# AUX_power_board.net
KiCad netlist of a schematic drawn in EAGLE
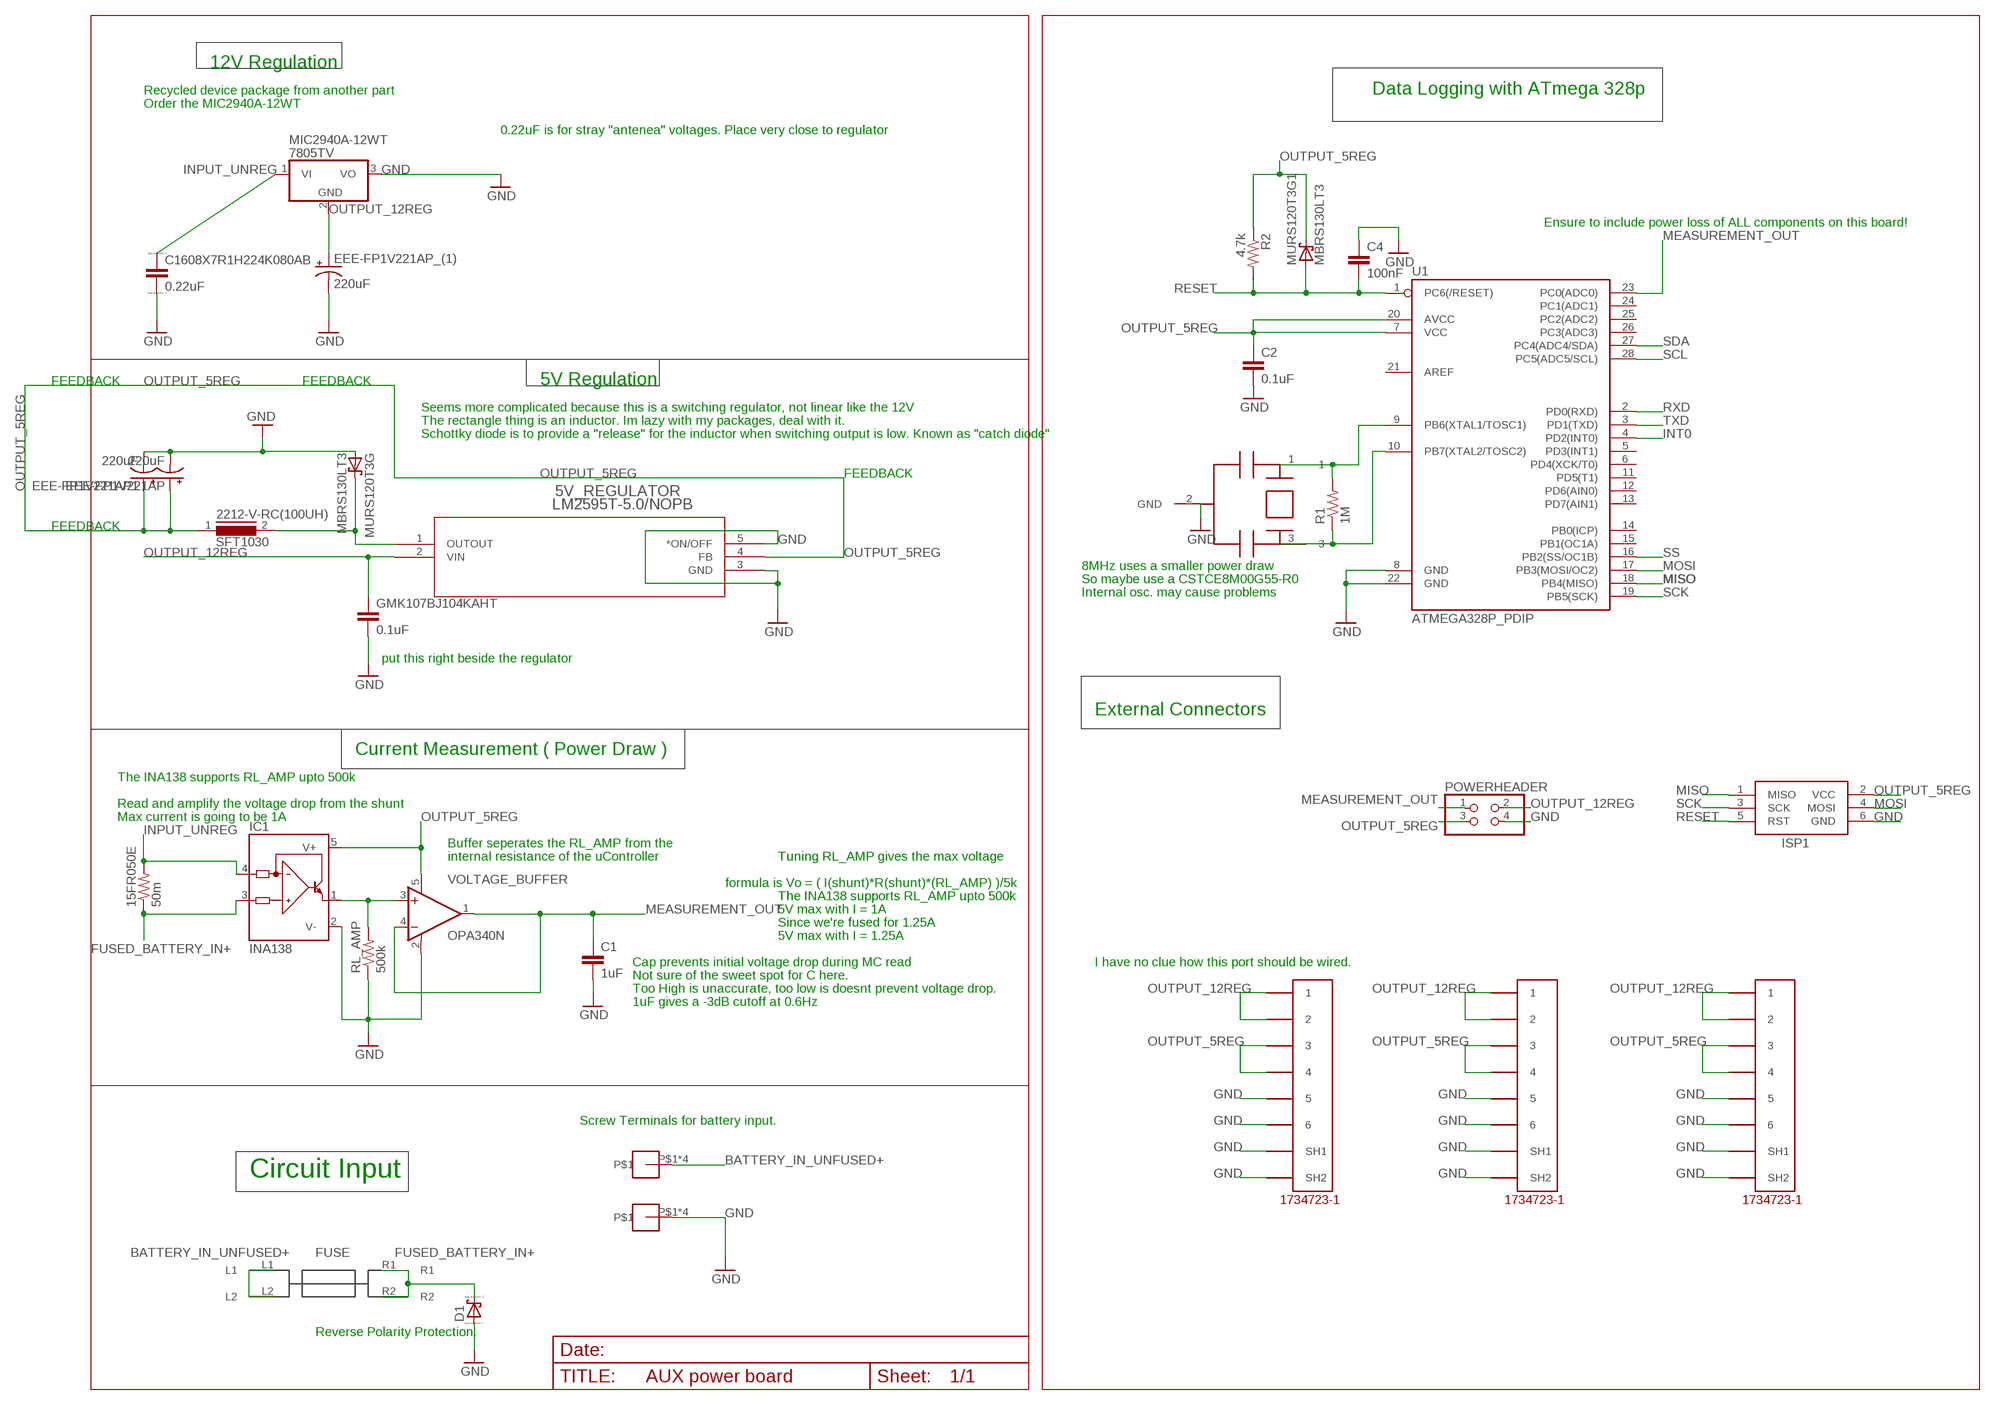
[diagram p0: schematic, sheet 1]

(export (version "E")
  (design (tool "Eeschema 10.0.6"))
  (components
    (comp (ref "5V_REGULATOR")
      (value "LM2595T-5.0/NOPB")
      (footprint "eagle-import:T05D")
      (fields
        (field (name "MANUFACTURER_PART_NUMBER") "LM2595T50")
        (field (name "COPYRIGHT") "Copyright C 2015 Accelerated Designs. All rights reserved")
      )
      (libsource (lib "eagle-import") (part "LM2595T-5.0/NOPB"))
    )
    (comp (ref "15FR050E")
      (value "50m")
      (footprint "eagle-import:0617_22")
      (libsource (lib "eagle-import") (part "resistor_R-US_0617/22"))
    )
    (comp (ref "2212-V-RC(100UH)")
      (value "SFT1030")
      (footprint "eagle-import:SFT1030")
      (libsource (lib "eagle-import") (part "SFT1030"))
    )
    (comp (ref "C1")
      (value "1uF")
      (footprint "eagle-import:C0603")
      (libsource (lib "eagle-import") (part "resistor_C-EUC0603"))
    )
    (comp (ref "C2")
      (value "0.1uF")
      (footprint "eagle-import:C0603")
      (libsource (lib "eagle-import") (part "resistor_C-EUC0603"))
    )
    (comp (ref "C4")
      (value "100nF")
      (footprint "eagle-import:C0603")
      (libsource (lib "eagle-import") (part "C-EUC0603"))
    )
    (comp (ref "C1608X7R1H224K080AB")
      (value "0.22uF")
      (footprint "eagle-import:C0603")
      (libsource (lib "eagle-import") (part "CC0603"))
    )
    (comp (ref "D1")
      (value "SCHOTTKY-DIODESMC")
      (footprint "eagle-import:DIODE_SMC")
      (libsource (lib "eagle-import") (part "SCHOTTKY-DIODESMC"))
    )
    (comp (ref "EEE-FP1V221AP")
      (value "220uF")
      (footprint "eagle-import:175TMP-0808")
      (libsource (lib "eagle-import") (part "CPOL-US175TMP-0808"))
    )
    (comp (ref "EEE-FP1V221AP1")
      (value "220uF")
      (footprint "eagle-import:175TMP-0808")
      (libsource (lib "eagle-import") (part "CPOL-US175TMP-0808"))
    )
    (comp (ref "EEE-FP1V221AP_(1)")
      (value "220uF")
      (footprint "eagle-import:175TMP-0808")
      (libsource (lib "eagle-import") (part "CPOL-US175TMP-0808"))
    )
    (comp (ref "GMK107BJ104KAHT")
      (value "0.1uF")
      (footprint "eagle-import:C0603")
      (libsource (lib "eagle-import") (part "C-EUC0603"))
    )
    (comp (ref "IC1")
      (value "INA138")
      (footprint "eagle-import:SOT23-5")
      (fields (field (name "MF") "TEXAS INSTRUMENTS") (field (name "MPN") "INA138NA/250"))
      (libsource (lib "eagle-import") (part "INA138"))
    )
    (comp (ref "ISP1")
      (value "AVRISP-6")
      (footprint "eagle-import:AVRISP")
      (libsource (lib "eagle-import") (part "AVRISP-6"))
    )
    (comp (ref "MIC2940A-12WT")
      (value "7805TV")
      (footprint "eagle-import:TO220V")
      (libsource (lib "eagle-import") (part "78TV05"))
    )
    (comp (ref "MINIBLADE")
      (value "3568")
      (footprint "eagle-import:3568")
      (libsource (lib "eagle-import") (part "3568"))
    )
    (comp (ref "MURS120T3G")
      (value "MBRS130LT3")
      (footprint "eagle-import:SMB")
      (libsource (lib "eagle-import") (part "MBRS130LT3"))
    )
    (comp (ref "MURS120T3G1")
      (value "MBRS130LT3")
      (footprint "eagle-import:SMB")
      (libsource (lib "eagle-import") (part "MBRS130LT3"))
    )
    (comp (ref "POWERHEADER")
      (value "PINHD-2X2")
      (footprint "eagle-import:2X02")
      (libsource (lib "eagle-import") (part "PINHD-2X2"))
    )
    (comp (ref "R1")
      (value "1M")
      (footprint "eagle-import:R0603")
      (libsource (lib "eagle-import") (part "R-US_R0603"))
    )
    (comp (ref "R2")
      (value "4.7k")
      (footprint "eagle-import:R0603")
      (libsource (lib "eagle-import") (part "resistor_R-US_R0603"))
    )
    (comp (ref "RL_AMP")
      (value "500k")
      (footprint "eagle-import:R0603")
      (libsource (lib "eagle-import") (part "resistor_R-US_R0603"))
    )
    (comp (ref "U$1")
      (value "CSTCE16M0V53-R0")
      (footprint "eagle-import:RESONATOR")
      (libsource (lib "eagle-import") (part "CSTCE16M0V53-R0"))
    )
    (comp (ref "U$3")
      (value "5555140-6")
      (footprint "eagle-import:1734723-1_RJ11")
      (libsource (lib "eagle-import") (part "5555140-6"))
    )
    (comp (ref "U$4")
      (value "5555140-6")
      (footprint "eagle-import:1734723-1_RJ11")
      (libsource (lib "eagle-import") (part "5555140-6"))
    )
    (comp (ref "U$5")
      (value "5555140-6")
      (footprint "eagle-import:1734723-1_RJ11")
      (libsource (lib "eagle-import") (part "5555140-6"))
    )
    (comp (ref "U$6")
      (value "SCREW-8191")
      (footprint "eagle-import:SCREW-8191")
      (libsource (lib "eagle-import") (part "SCREW-8191"))
    )
    (comp (ref "U$7")
      (value "SCREW-8191")
      (footprint "eagle-import:SCREW-8191")
      (libsource (lib "eagle-import") (part "SCREW-8191"))
    )
    (comp (ref "U1")
      (value "ATMEGA328P_PDIP")
      (footprint "eagle-import:DIL28-3")
      (libsource (lib "eagle-import") (part "ATMEGA328P_PDIP"))
    )
    (comp (ref "VOLTAGE_BUFFER")
      (value "OPA340N")
      (footprint "eagle-import:SOT23-5")
      (fields (field (name "MPN") "OPA340NA/3KG4"))
      (libsource (lib "eagle-import") (part "OPA340N"))
    )
  )
  (nets
    (net (code "1") (name "/BATTERY_IN_UNFUSED+") (class "Default")
      (node (ref "MINIBLADE") (pin "L1") (pinfunction "L1_L1") (pintype "bidirectional"))
      (node (ref "MINIBLADE") (pin "L2") (pinfunction "L2_L2") (pintype "bidirectional"))
      (node (ref "U$6") (pin "P$1") (pinfunction "P$1_P$1") (pintype "bidirectional"))
      (node (ref "U$6") (pin "P$2") (pinfunction "P$1_P$2") (pintype "bidirectional"))
      (node (ref "U$6") (pin "P$3") (pinfunction "P$1_P$3") (pintype "bidirectional"))
      (node (ref "U$6") (pin "P$4") (pinfunction "P$1_P$4") (pintype "bidirectional"))
    )
    (net (code "2") (name "/FUSED_BATTERY_IN+") (class "Default")
      (node (ref "15FR050E") (pin "1") (pinfunction "1_1") (pintype "passive"))
      (node (ref "D1") (pin "C") (pinfunction "A_C") (pintype "passive"))
      (node (ref "IC1") (pin "3") (pinfunction "IN+_3") (pintype "input"))
      (node (ref "MINIBLADE") (pin "R1") (pinfunction "R1_R1") (pintype "bidirectional"))
      (node (ref "MINIBLADE") (pin "R2") (pinfunction "R2_R2") (pintype "bidirectional"))
    )
    (net (code "3") (name "/INPUT_UNREG") (class "Default")
      (node (ref "15FR050E") (pin "2") (pinfunction "2_2") (pintype "passive"))
      (node (ref "C1608X7R1H224K080AB") (pin "1") (pinfunction "1_1") (pintype "passive"))
      (node (ref "IC1") (pin "4") (pinfunction "IN-_4") (pintype "input"))
      (node (ref "MIC2940A-12WT") (pin "1") (pinfunction "VI_1") (pintype "input"))
    )
    (net (code "4") (name "/INT0") (class "Default")
      (node (ref "U1") (pin "4") (pinfunction "PD2(INT0)_4") (pintype "bidirectional"))
    )
    (net (code "5") (name "/MEASUREMENT_OUT") (class "Default")
      (node (ref "C1") (pin "1") (pinfunction "1_1") (pintype "passive"))
      (node (ref "POWERHEADER") (pin "1") (pinfunction "1_1") (pintype "passive"))
      (node (ref "U1") (pin "23") (pinfunction "PC0(ADC0)_23") (pintype "bidirectional"))
      (node (ref "VOLTAGE_BUFFER") (pin "1") (pinfunction "OUT_1") (pintype "output"))
      (node (ref "VOLTAGE_BUFFER") (pin "4") (pinfunction "-IN_4") (pintype "input"))
    )
    (net (code "6") (name "/MISO") (class "Default")
      (node (ref "ISP1") (pin "1") (pinfunction "MISO_1") (pintype "input"))
      (node (ref "U1") (pin "18") (pinfunction "PB4(MISO)_18") (pintype "bidirectional"))
    )
    (net (code "7") (name "/MOSI") (class "Default")
      (node (ref "ISP1") (pin "4") (pinfunction "MOSI_4") (pintype "output"))
      (node (ref "U1") (pin "17") (pinfunction "PB3(MOSI/OC2)_17") (pintype "bidirectional"))
    )
    (net (code "8") (name "/OUTPUT_5REG") (class "Default")
      (node (ref "2212-V-RC(100UH)") (pin "1") (pinfunction "1_1") (pintype "passive"))
      (node (ref "5V_REGULATOR") (pin "4") (pinfunction "FB_4") (pintype "passive"))
      (node (ref "C2") (pin "1") (pinfunction "1_1") (pintype "passive"))
      (node (ref "EEE-FP1V221AP") (pin "+") (pinfunction "+_+") (pintype "passive"))
      (node (ref "EEE-FP1V221AP1") (pin "+") (pinfunction "+_+") (pintype "passive"))
      (node (ref "IC1") (pin "5") (pinfunction "V+_5") (pintype "power_in"))
      (node (ref "ISP1") (pin "2") (pinfunction "VCC_2") (pintype "power_in"))
      (node (ref "MURS120T3G1") (pin "C") (pinfunction "C_C") (pintype "passive"))
      (node (ref "POWERHEADER") (pin "3") (pinfunction "3_3") (pintype "passive"))
      (node (ref "R2") (pin "1") (pinfunction "1_1") (pintype "passive"))
      (node (ref "U$3") (pin "3") (pinfunction "3_3") (pintype "bidirectional"))
      (node (ref "U$3") (pin "4") (pinfunction "4_4") (pintype "bidirectional"))
      (node (ref "U$4") (pin "3") (pinfunction "3_3") (pintype "bidirectional"))
      (node (ref "U$4") (pin "4") (pinfunction "4_4") (pintype "bidirectional"))
      (node (ref "U$5") (pin "3") (pinfunction "3_3") (pintype "bidirectional"))
      (node (ref "U$5") (pin "4") (pinfunction "4_4") (pintype "bidirectional"))
      (node (ref "U1") (pin "20") (pinfunction "AVCC_20") (pintype "bidirectional"))
      (node (ref "U1") (pin "7") (pinfunction "VCC_7") (pintype "bidirectional"))
      (node (ref "VOLTAGE_BUFFER") (pin "5") (pinfunction "V+_5") (pintype "power_in"))
    )
    (net (code "9") (name "/OUTPUT_12REG") (class "Default")
      (node (ref "5V_REGULATOR") (pin "2") (pinfunction "VIN_2") (pintype "input"))
      (node (ref "EEE-FP1V221AP_(1)") (pin "+") (pinfunction "+_+") (pintype "passive"))
      (node (ref "GMK107BJ104KAHT") (pin "1") (pinfunction "1_1") (pintype "passive"))
      (node (ref "MIC2940A-12WT") (pin "2") (pinfunction "GND_2") (pintype "passive"))
      (node (ref "POWERHEADER") (pin "2") (pinfunction "2_2") (pintype "passive"))
      (node (ref "U$3") (pin "1") (pinfunction "1_1") (pintype "bidirectional"))
      (node (ref "U$3") (pin "2") (pinfunction "2_2") (pintype "bidirectional"))
      (node (ref "U$4") (pin "1") (pinfunction "1_1") (pintype "bidirectional"))
      (node (ref "U$4") (pin "2") (pinfunction "2_2") (pintype "bidirectional"))
      (node (ref "U$5") (pin "1") (pinfunction "1_1") (pintype "bidirectional"))
      (node (ref "U$5") (pin "2") (pinfunction "2_2") (pintype "bidirectional"))
    )
    (net (code "10") (name "/RESET") (class "Default")
      (node (ref "C4") (pin "2") (pinfunction "2_2") (pintype "passive"))
      (node (ref "ISP1") (pin "5") (pinfunction "RST_5") (pintype "output"))
      (node (ref "MURS120T3G1") (pin "A") (pinfunction "A_A") (pintype "passive"))
      (node (ref "R2") (pin "2") (pinfunction "2_2") (pintype "passive"))
      (node (ref "U1") (pin "1") (pinfunction "PC6(/RESET)_1") (pintype "bidirectional"))
    )
    (net (code "11") (name "/RXD") (class "Default")
      (node (ref "U1") (pin "2") (pinfunction "PD0(RXD)_2") (pintype "bidirectional"))
    )
    (net (code "12") (name "/SCK") (class "Default")
      (node (ref "ISP1") (pin "3") (pinfunction "SCK_3") (pintype "output"))
      (node (ref "U1") (pin "19") (pinfunction "PB5(SCK)_19") (pintype "bidirectional"))
    )
    (net (code "13") (name "/SCL") (class "Default")
      (node (ref "U1") (pin "28") (pinfunction "PC5(ADC5/SCL)_28") (pintype "bidirectional"))
    )
    (net (code "14") (name "/SDA") (class "Default")
      (node (ref "U1") (pin "27") (pinfunction "PC4(ADC4/SDA)_27") (pintype "bidirectional"))
    )
    (net (code "15") (name "/SS") (class "Default")
      (node (ref "U1") (pin "16") (pinfunction "PB2(SS/OC1B)_16") (pintype "bidirectional"))
    )
    (net (code "16") (name "/TXD") (class "Default")
      (node (ref "U1") (pin "3") (pinfunction "PD1(TXD)_3") (pintype "bidirectional"))
    )
    (net (code "17") (name "GND") (class "Default")
      (node (ref "5V_REGULATOR") (pin "3") (pinfunction "GND_3") (pintype "passive"))
      (node (ref "5V_REGULATOR") (pin "5") (pinfunction "*ON/OFF_5") (pintype "passive"))
      (node (ref "C1") (pin "2") (pinfunction "2_2") (pintype "passive"))
      (node (ref "C1608X7R1H224K080AB") (pin "2") (pinfunction "2_2") (pintype "passive"))
      (node (ref "C2") (pin "2") (pinfunction "2_2") (pintype "passive"))
      (node (ref "C4") (pin "1") (pinfunction "1_1") (pintype "passive"))
      (node (ref "D1") (pin "A") (pinfunction "C_A") (pintype "passive"))
      (node (ref "EEE-FP1V221AP") (pin "-") (pinfunction "-_-") (pintype "passive"))
      (node (ref "EEE-FP1V221AP1") (pin "-") (pinfunction "-_-") (pintype "passive"))
      (node (ref "EEE-FP1V221AP_(1)") (pin "-") (pinfunction "-_-") (pintype "passive"))
      (node (ref "GMK107BJ104KAHT") (pin "2") (pinfunction "2_2") (pintype "passive"))
      (node (ref "IC1") (pin "2") (pinfunction "V-_2") (pintype "power_in"))
      (node (ref "ISP1") (pin "6") (pinfunction "GND_6") (pintype "power_in"))
      (node (ref "MIC2940A-12WT") (pin "3") (pinfunction "VO_3") (pintype "passive"))
      (node (ref "MURS120T3G") (pin "A") (pinfunction "A_A") (pintype "passive"))
      (node (ref "POWERHEADER") (pin "4") (pinfunction "4_4") (pintype "passive"))
      (node (ref "RL_AMP") (pin "1") (pinfunction "1_1") (pintype "passive"))
      (node (ref "U$1") (pin "2") (pinfunction "GND_2") (pintype "bidirectional"))
      (node (ref "U$3") (pin "5") (pinfunction "5_5") (pintype "bidirectional"))
      (node (ref "U$3") (pin "6") (pinfunction "6_6") (pintype "bidirectional"))
      (node (ref "U$3") (pin "SH1") (pinfunction "SH1_SH1") (pintype "bidirectional"))
      (node (ref "U$3") (pin "SH2") (pinfunction "SH2_SH2") (pintype "bidirectional"))
      (node (ref "U$4") (pin "5") (pinfunction "5_5") (pintype "bidirectional"))
      (node (ref "U$4") (pin "6") (pinfunction "6_6") (pintype "bidirectional"))
      (node (ref "U$4") (pin "SH1") (pinfunction "SH1_SH1") (pintype "bidirectional"))
      (node (ref "U$4") (pin "SH2") (pinfunction "SH2_SH2") (pintype "bidirectional"))
      (node (ref "U$5") (pin "5") (pinfunction "5_5") (pintype "bidirectional"))
      (node (ref "U$5") (pin "6") (pinfunction "6_6") (pintype "bidirectional"))
      (node (ref "U$5") (pin "SH1") (pinfunction "SH1_SH1") (pintype "bidirectional"))
      (node (ref "U$5") (pin "SH2") (pinfunction "SH2_SH2") (pintype "bidirectional"))
      (node (ref "U$7") (pin "P$1") (pinfunction "P$1_P$1") (pintype "bidirectional"))
      (node (ref "U$7") (pin "P$2") (pinfunction "P$1_P$2") (pintype "bidirectional"))
      (node (ref "U$7") (pin "P$3") (pinfunction "P$1_P$3") (pintype "bidirectional"))
      (node (ref "U$7") (pin "P$4") (pinfunction "P$1_P$4") (pintype "bidirectional"))
      (node (ref "U1") (pin "22") (pinfunction "GND_22") (pintype "bidirectional"))
      (node (ref "U1") (pin "8") (pinfunction "GND_8") (pintype "bidirectional"))
      (node (ref "VOLTAGE_BUFFER") (pin "2") (pinfunction "V-_2") (pintype "power_in"))
    )
    (net (code "18") (name "Net-(5V_REGULATOR-OUTOUT)") (class "Default")
      (node (ref "2212-V-RC(100UH)") (pin "2") (pinfunction "2_2") (pintype "passive"))
      (node (ref "5V_REGULATOR") (pin "1") (pinfunction "OUTOUT_1") (pintype "output"))
      (node (ref "MURS120T3G") (pin "C") (pinfunction "C_C") (pintype "passive"))
    )
    (net (code "19") (name "Net-(IC1-OUT)") (class "Default")
      (node (ref "IC1") (pin "1") (pinfunction "OUT_1") (pintype "output"))
      (node (ref "RL_AMP") (pin "2") (pinfunction "2_2") (pintype "passive"))
      (node (ref "VOLTAGE_BUFFER") (pin "3") (pinfunction "+IN_3") (pintype "input"))
    )
    (net (code "20") (name "Net-(U1-PB6(XTAL1{slash}TOSC1))") (class "Default")
      (node (ref "R1") (pin "2") (pinfunction "2_2") (pintype "passive"))
      (node (ref "U$1") (pin "1") (pinfunction "1_1") (pintype "bidirectional"))
      (node (ref "U1") (pin "9") (pinfunction "PB6(XTAL1/TOSC1)_9") (pintype "bidirectional"))
    )
    (net (code "21") (name "Net-(U1-PB7(XTAL2{slash}TOSC2))") (class "Default")
      (node (ref "R1") (pin "1") (pinfunction "1_1") (pintype "passive"))
      (node (ref "U$1") (pin "3") (pinfunction "3_3") (pintype "bidirectional"))
      (node (ref "U1") (pin "10") (pinfunction "PB7(XTAL2/TOSC2)_10") (pintype "bidirectional"))
    )
    (net (code "22") (name "unconnected-(U1-AREF-Pad21)") (class "Default")
      (node (ref "U1") (pin "21") (pinfunction "AREF_21") (pintype "bidirectional"))
    )
    (net (code "23") (name "unconnected-(U1-PB0(ICP)-Pad14)") (class "Default")
      (node (ref "U1") (pin "14") (pinfunction "PB0(ICP)_14") (pintype "bidirectional"))
    )
    (net (code "24") (name "unconnected-(U1-PB1(OC1A)-Pad15)") (class "Default")
      (node (ref "U1") (pin "15") (pinfunction "PB1(OC1A)_15") (pintype "bidirectional"))
    )
    (net (code "25") (name "unconnected-(U1-PC1(ADC1)-Pad24)") (class "Default")
      (node (ref "U1") (pin "24") (pinfunction "PC1(ADC1)_24") (pintype "bidirectional"))
    )
    (net (code "26") (name "unconnected-(U1-PC2(ADC2)-Pad25)") (class "Default")
      (node (ref "U1") (pin "25") (pinfunction "PC2(ADC2)_25") (pintype "bidirectional"))
    )
    (net (code "27") (name "unconnected-(U1-PC3(ADC3)-Pad26)") (class "Default")
      (node (ref "U1") (pin "26") (pinfunction "PC3(ADC3)_26") (pintype "bidirectional"))
    )
    (net (code "28") (name "unconnected-(U1-PD3(INT1)-Pad5)") (class "Default")
      (node (ref "U1") (pin "5") (pinfunction "PD3(INT1)_5") (pintype "bidirectional"))
    )
    (net (code "29") (name "unconnected-(U1-PD4(XCK{slash}T0)-Pad6)") (class "Default")
      (node (ref "U1") (pin "6") (pinfunction "PD4(XCK/T0)_6") (pintype "bidirectional"))
    )
    (net (code "30") (name "unconnected-(U1-PD5(T1)-Pad11)") (class "Default")
      (node (ref "U1") (pin "11") (pinfunction "PD5(T1)_11") (pintype "bidirectional"))
    )
    (net (code "31") (name "unconnected-(U1-PD6(AIN0)-Pad12)") (class "Default")
      (node (ref "U1") (pin "12") (pinfunction "PD6(AIN0)_12") (pintype "bidirectional"))
    )
    (net (code "32") (name "unconnected-(U1-PD7(AIN1)-Pad13)") (class "Default")
      (node (ref "U1") (pin "13") (pinfunction "PD7(AIN1)_13") (pintype "bidirectional"))
    )
  )
)
